# hassisPartSCH.net
KiCad netlist of a schematic drawn in Altium Designer
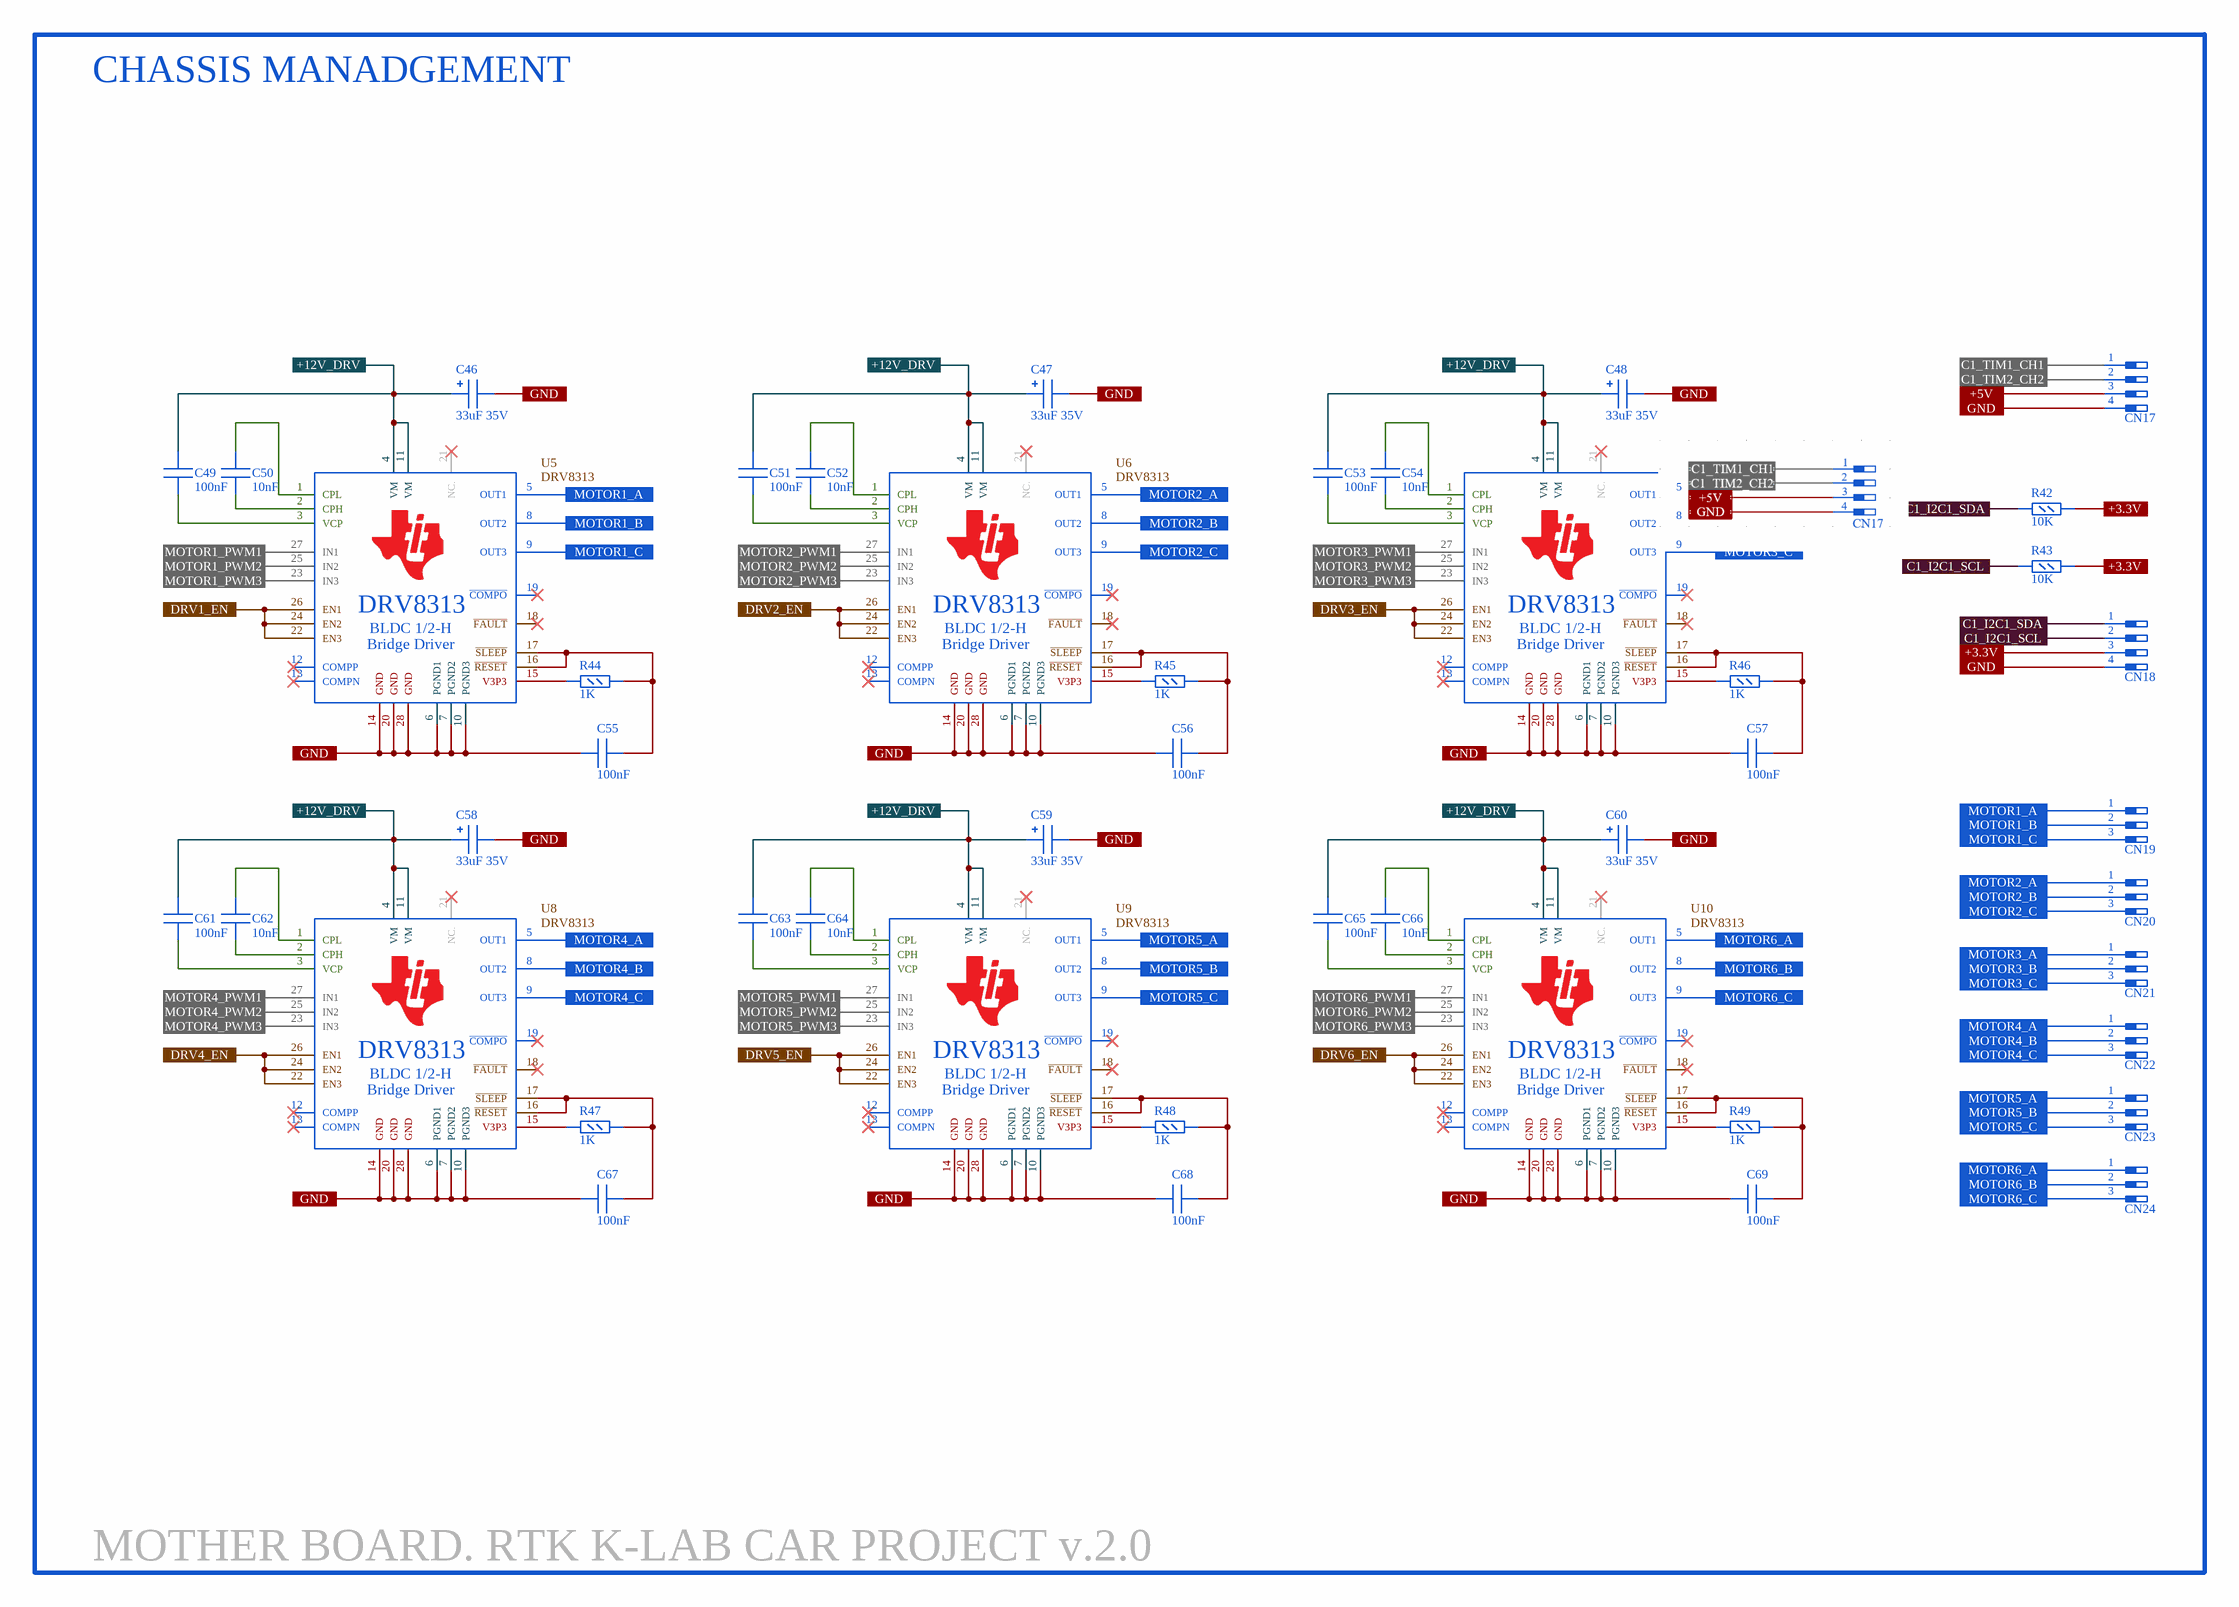
[diagram p0: СhassisPartSCH.SchDoc]

(export (version "E")
  (design (tool "Eeschema 10.0.6"))
  (components
    (comp (ref "C46")
      (value "33uF 35V")
      (footprint "CAP_TAN-B")
      (libsource (lib "CustomMillLib_Col") (part "Cap_Pol"))
    )
    (comp (ref "C47")
      (value "33uF 35V")
      (footprint "CAP_TAN-B")
      (libsource (lib "CustomMillLib_Col") (part "Cap_Pol"))
    )
    (comp (ref "C48")
      (value "33uF 35V")
      (footprint "CAP_TAN-B")
      (libsource (lib "CustomMillLib_Col") (part "Cap_Pol"))
    )
    (comp (ref "C49") (value "100nF") (footprint "C0603") (libsource (lib "CommonElements") (part "Cap")))
    (comp (ref "C50") (value "10nF") (footprint "C0603") (libsource (lib "CommonElements") (part "Cap")))
    (comp (ref "C51") (value "100nF") (footprint "C0603") (libsource (lib "CommonElements") (part "Cap")))
    (comp (ref "C52") (value "10nF") (footprint "C0603") (libsource (lib "CommonElements") (part "Cap")))
    (comp (ref "C53") (value "100nF") (footprint "C0603") (libsource (lib "CommonElements") (part "Cap")))
    (comp (ref "C54") (value "10nF") (footprint "C0603") (libsource (lib "CommonElements") (part "Cap")))
    (comp (ref "C55") (value "100nF") (footprint "C0603") (libsource (lib "CommonElements") (part "Cap")))
    (comp (ref "C56") (value "100nF") (footprint "C0603") (libsource (lib "CommonElements") (part "Cap")))
    (comp (ref "C57") (value "100nF") (footprint "C0603") (libsource (lib "CommonElements") (part "Cap")))
    (comp (ref "C58")
      (value "33uF 35V")
      (footprint "CAP_TAN-B")
      (libsource (lib "CustomMillLib_Col") (part "Cap_Pol"))
    )
    (comp (ref "C59")
      (value "33uF 35V")
      (footprint "CAP_TAN-B")
      (libsource (lib "CustomMillLib_Col") (part "Cap_Pol"))
    )
    (comp (ref "C60")
      (value "33uF 35V")
      (footprint "CAP_TAN-B")
      (libsource (lib "CustomMillLib_Col") (part "Cap_Pol"))
    )
    (comp (ref "C61") (value "100nF") (footprint "C0603") (libsource (lib "CommonElements") (part "Cap")))
    (comp (ref "C62") (value "10nF") (footprint "C0603") (libsource (lib "CommonElements") (part "Cap")))
    (comp (ref "C63") (value "100nF") (footprint "C0603") (libsource (lib "CommonElements") (part "Cap")))
    (comp (ref "C64") (value "10nF") (footprint "C0603") (libsource (lib "CommonElements") (part "Cap")))
    (comp (ref "C65") (value "100nF") (footprint "C0603") (libsource (lib "CommonElements") (part "Cap")))
    (comp (ref "C66") (value "10nF") (footprint "C0603") (libsource (lib "CommonElements") (part "Cap")))
    (comp (ref "C67") (value "100nF") (footprint "C0603") (libsource (lib "CommonElements") (part "Cap")))
    (comp (ref "C68") (value "100nF") (footprint "C0603") (libsource (lib "CommonElements") (part "Cap")))
    (comp (ref "C69") (value "100nF") (footprint "C0603") (libsource (lib "CommonElements") (part "Cap")))
    (comp (ref "CN17") (value "1x04") (footprint "4X1F") (libsource (lib "Connectors") (part "1x04")))
    (comp (ref "CN18") (value "1x04") (footprint "XH2.54-4PIN") (libsource (lib "Connectors") (part "1x04")))
    (comp (ref "CN19") (value "1x03") (footprint "H3-5.08") (libsource (lib "Connectors") (part "1x03")))
    (comp (ref "CN20") (value "1x03") (footprint "H3-5.08") (libsource (lib "Connectors") (part "1x03")))
    (comp (ref "CN21") (value "1x03") (footprint "H3-5.08") (libsource (lib "Connectors") (part "1x03")))
    (comp (ref "CN22") (value "1x03") (footprint "H3-5.08") (libsource (lib "Connectors") (part "1x03")))
    (comp (ref "CN23") (value "1x03") (footprint "H3-5.08") (libsource (lib "Connectors") (part "1x03")))
    (comp (ref "CN24") (value "1x03") (footprint "H3-5.08") (libsource (lib "Connectors") (part "1x03")))
    (comp (ref "R42") (value "10K") (footprint "R0603") (libsource (lib "CommonElements") (part "Res")))
    (comp (ref "R43") (value "10K") (footprint "R0603") (libsource (lib "CommonElements") (part "Res")))
    (comp (ref "R44") (value "1K") (footprint "R0603") (libsource (lib "CommonElements") (part "Res")))
    (comp (ref "R45") (value "1K") (footprint "R0603") (libsource (lib "CommonElements") (part "Res")))
    (comp (ref "R46") (value "1K") (footprint "R0603") (libsource (lib "CommonElements") (part "Res")))
    (comp (ref "R47") (value "1K") (footprint "R0603") (libsource (lib "CommonElements") (part "Res")))
    (comp (ref "R48") (value "1K") (footprint "R0603") (libsource (lib "CommonElements") (part "Res")))
    (comp (ref "R49") (value "1K") (footprint "R0603") (libsource (lib "CommonElements") (part "Res")))
    (comp (ref "U5")
      (value "DRV8313")
      (footprint "TSSOP28-TP")
      (libsource (lib "DigitalUnits") (part "DRV8313"))
    )
    (comp (ref "U6")
      (value "DRV8313")
      (footprint "TSSOP28-TP")
      (libsource (lib "DigitalUnits") (part "DRV8313"))
    )
    (comp (ref "U7")
      (value "DRV8313")
      (footprint "TSSOP28-TP")
      (libsource (lib "DigitalUnits") (part "DRV8313"))
    )
    (comp (ref "U8")
      (value "DRV8313")
      (footprint "TSSOP28-TP")
      (libsource (lib "DigitalUnits") (part "DRV8313"))
    )
    (comp (ref "U9")
      (value "DRV8313")
      (footprint "TSSOP28-TP")
      (libsource (lib "DigitalUnits") (part "DRV8313"))
    )
    (comp (ref "U10")
      (value "DRV8313")
      (footprint "TSSOP28-TP")
      (libsource (lib "DigitalUnits") (part "DRV8313"))
    )
  )
  (nets
    (net (code "1") (name "/+3.3V") (class "Default")
      (node (ref "CN18") (pin "3") (pintype "passive"))
      (node (ref "R42") (pin "2") (pinfunction "2_2") (pintype "passive"))
      (node (ref "R43") (pin "2") (pinfunction "2_2") (pintype "passive"))
    )
    (net (code "2") (name "/+5V") (class "Default") (node (ref "CN17") (pin "3") (pintype "passive")))
    (net (code "3") (name "/+12V_DRV") (class "Default")
      (node (ref "C46") (pin "1") (pinfunction "61_1") (pintype "passive"))
      (node (ref "C47") (pin "1") (pinfunction "61_1") (pintype "passive"))
      (node (ref "C48") (pin "1") (pinfunction "61_1") (pintype "passive"))
      (node (ref "C49") (pin "2") (pinfunction "62_2") (pintype "passive"))
      (node (ref "C51") (pin "2") (pinfunction "62_2") (pintype "passive"))
      (node (ref "C53") (pin "2") (pinfunction "62_2") (pintype "passive"))
      (node (ref "C58") (pin "1") (pinfunction "61_1") (pintype "passive"))
      (node (ref "C59") (pin "1") (pinfunction "61_1") (pintype "passive"))
      (node (ref "C60") (pin "1") (pinfunction "61_1") (pintype "passive"))
      (node (ref "C61") (pin "2") (pinfunction "62_2") (pintype "passive"))
      (node (ref "C63") (pin "2") (pinfunction "62_2") (pintype "passive"))
      (node (ref "C65") (pin "2") (pinfunction "62_2") (pintype "passive"))
      (node (ref "U10") (pin "11") (pinfunction "VM_11") (pintype "passive"))
      (node (ref "U10") (pin "4") (pinfunction "VM_4") (pintype "passive"))
      (node (ref "U5") (pin "11") (pinfunction "VM_11") (pintype "passive"))
      (node (ref "U5") (pin "4") (pinfunction "VM_4") (pintype "passive"))
      (node (ref "U6") (pin "11") (pinfunction "VM_11") (pintype "passive"))
      (node (ref "U6") (pin "4") (pinfunction "VM_4") (pintype "passive"))
      (node (ref "U7") (pin "11") (pinfunction "VM_11") (pintype "passive"))
      (node (ref "U7") (pin "4") (pinfunction "VM_4") (pintype "passive"))
      (node (ref "U8") (pin "11") (pinfunction "VM_11") (pintype "passive"))
      (node (ref "U8") (pin "4") (pinfunction "VM_4") (pintype "passive"))
      (node (ref "U9") (pin "11") (pinfunction "VM_11") (pintype "passive"))
      (node (ref "U9") (pin "4") (pinfunction "VM_4") (pintype "passive"))
    )
    (net (code "4") (name "/C1_I2C1_SCL") (class "Default")
      (node (ref "CN18") (pin "2") (pintype "passive"))
      (node (ref "R43") (pin "1") (pinfunction "2_1") (pintype "passive"))
    )
    (net (code "5") (name "/C1_I2C1_SDA") (class "Default")
      (node (ref "CN18") (pin "1") (pintype "passive"))
      (node (ref "R42") (pin "1") (pinfunction "2_1") (pintype "passive"))
    )
    (net (code "6") (name "/C1_TIM1_CH1") (class "Default") (node (ref "CN17") (pin "1") (pintype "passive")))
    (net (code "7") (name "/C1_TIM2_CH2") (class "Default") (node (ref "CN17") (pin "2") (pintype "passive")))
    (net (code "8") (name "/DRV1_EN") (class "Default")
      (node (ref "U5") (pin "22") (pinfunction "EN3_22") (pintype "passive"))
      (node (ref "U5") (pin "24") (pinfunction "EN2_24") (pintype "passive"))
      (node (ref "U5") (pin "26") (pinfunction "EN1_26") (pintype "passive"))
    )
    (net (code "9") (name "/DRV2_EN") (class "Default")
      (node (ref "U6") (pin "22") (pinfunction "EN3_22") (pintype "passive"))
      (node (ref "U6") (pin "24") (pinfunction "EN2_24") (pintype "passive"))
      (node (ref "U6") (pin "26") (pinfunction "EN1_26") (pintype "passive"))
    )
    (net (code "10") (name "/DRV3_EN") (class "Default")
      (node (ref "U7") (pin "22") (pinfunction "EN3_22") (pintype "passive"))
      (node (ref "U7") (pin "24") (pinfunction "EN2_24") (pintype "passive"))
      (node (ref "U7") (pin "26") (pinfunction "EN1_26") (pintype "passive"))
    )
    (net (code "11") (name "/DRV4_EN") (class "Default")
      (node (ref "U8") (pin "22") (pinfunction "EN3_22") (pintype "passive"))
      (node (ref "U8") (pin "24") (pinfunction "EN2_24") (pintype "passive"))
      (node (ref "U8") (pin "26") (pinfunction "EN1_26") (pintype "passive"))
    )
    (net (code "12") (name "/DRV5_EN") (class "Default")
      (node (ref "U9") (pin "22") (pinfunction "EN3_22") (pintype "passive"))
      (node (ref "U9") (pin "24") (pinfunction "EN2_24") (pintype "passive"))
      (node (ref "U9") (pin "26") (pinfunction "EN1_26") (pintype "passive"))
    )
    (net (code "13") (name "/DRV6_EN") (class "Default")
      (node (ref "U10") (pin "22") (pinfunction "EN3_22") (pintype "passive"))
      (node (ref "U10") (pin "24") (pinfunction "EN2_24") (pintype "passive"))
      (node (ref "U10") (pin "26") (pinfunction "EN1_26") (pintype "passive"))
    )
    (net (code "14") (name "/GND") (class "Default")
      (node (ref "C46") (pin "2") (pinfunction "62_2") (pintype "passive"))
      (node (ref "C47") (pin "2") (pinfunction "62_2") (pintype "passive"))
      (node (ref "C48") (pin "2") (pinfunction "62_2") (pintype "passive"))
      (node (ref "C55") (pin "1") (pinfunction "61_1") (pintype "passive"))
      (node (ref "C56") (pin "1") (pinfunction "61_1") (pintype "passive"))
      (node (ref "C57") (pin "1") (pinfunction "61_1") (pintype "passive"))
      (node (ref "C58") (pin "2") (pinfunction "62_2") (pintype "passive"))
      (node (ref "C59") (pin "2") (pinfunction "62_2") (pintype "passive"))
      (node (ref "C60") (pin "2") (pinfunction "62_2") (pintype "passive"))
      (node (ref "C67") (pin "1") (pinfunction "61_1") (pintype "passive"))
      (node (ref "C68") (pin "1") (pinfunction "61_1") (pintype "passive"))
      (node (ref "C69") (pin "1") (pinfunction "61_1") (pintype "passive"))
      (node (ref "CN17") (pin "4") (pintype "passive"))
      (node (ref "CN18") (pin "4") (pintype "passive"))
      (node (ref "U10") (pin "10") (pinfunction "PGND3_10") (pintype "passive"))
      (node (ref "U10") (pin "14") (pinfunction "GND_14") (pintype "passive"))
      (node (ref "U10") (pin "20") (pinfunction "GND_20") (pintype "passive"))
      (node (ref "U10") (pin "28") (pinfunction "GND_28") (pintype "passive"))
      (node (ref "U10") (pin "6") (pinfunction "PGND1_6") (pintype "passive"))
      (node (ref "U10") (pin "7") (pinfunction "PGND2_7") (pintype "passive"))
      (node (ref "U5") (pin "10") (pinfunction "PGND3_10") (pintype "passive"))
      (node (ref "U5") (pin "14") (pinfunction "GND_14") (pintype "passive"))
      (node (ref "U5") (pin "20") (pinfunction "GND_20") (pintype "passive"))
      (node (ref "U5") (pin "28") (pinfunction "GND_28") (pintype "passive"))
      (node (ref "U5") (pin "6") (pinfunction "PGND1_6") (pintype "passive"))
      (node (ref "U5") (pin "7") (pinfunction "PGND2_7") (pintype "passive"))
      (node (ref "U6") (pin "10") (pinfunction "PGND3_10") (pintype "passive"))
      (node (ref "U6") (pin "14") (pinfunction "GND_14") (pintype "passive"))
      (node (ref "U6") (pin "20") (pinfunction "GND_20") (pintype "passive"))
      (node (ref "U6") (pin "28") (pinfunction "GND_28") (pintype "passive"))
      (node (ref "U6") (pin "6") (pinfunction "PGND1_6") (pintype "passive"))
      (node (ref "U6") (pin "7") (pinfunction "PGND2_7") (pintype "passive"))
      (node (ref "U7") (pin "10") (pinfunction "PGND3_10") (pintype "passive"))
      (node (ref "U7") (pin "14") (pinfunction "GND_14") (pintype "passive"))
      (node (ref "U7") (pin "20") (pinfunction "GND_20") (pintype "passive"))
      (node (ref "U7") (pin "28") (pinfunction "GND_28") (pintype "passive"))
      (node (ref "U7") (pin "6") (pinfunction "PGND1_6") (pintype "passive"))
      (node (ref "U7") (pin "7") (pinfunction "PGND2_7") (pintype "passive"))
      (node (ref "U8") (pin "10") (pinfunction "PGND3_10") (pintype "passive"))
      (node (ref "U8") (pin "14") (pinfunction "GND_14") (pintype "passive"))
      (node (ref "U8") (pin "20") (pinfunction "GND_20") (pintype "passive"))
      (node (ref "U8") (pin "28") (pinfunction "GND_28") (pintype "passive"))
      (node (ref "U8") (pin "6") (pinfunction "PGND1_6") (pintype "passive"))
      (node (ref "U8") (pin "7") (pinfunction "PGND2_7") (pintype "passive"))
      (node (ref "U9") (pin "10") (pinfunction "PGND3_10") (pintype "passive"))
      (node (ref "U9") (pin "14") (pinfunction "GND_14") (pintype "passive"))
      (node (ref "U9") (pin "20") (pinfunction "GND_20") (pintype "passive"))
      (node (ref "U9") (pin "28") (pinfunction "GND_28") (pintype "passive"))
      (node (ref "U9") (pin "6") (pinfunction "PGND1_6") (pintype "passive"))
      (node (ref "U9") (pin "7") (pinfunction "PGND2_7") (pintype "passive"))
    )
    (net (code "15") (name "/MOTOR1_A") (class "Default")
      (node (ref "CN19") (pin "1") (pintype "passive"))
      (node (ref "U5") (pin "5") (pinfunction "OUT1_5") (pintype "passive"))
    )
    (net (code "16") (name "/MOTOR1_B") (class "Default")
      (node (ref "CN19") (pin "2") (pintype "passive"))
      (node (ref "U5") (pin "8") (pinfunction "OUT2_8") (pintype "passive"))
    )
    (net (code "17") (name "/MOTOR1_C") (class "Default")
      (node (ref "CN19") (pin "3") (pintype "passive"))
      (node (ref "U5") (pin "9") (pinfunction "OUT3_9") (pintype "passive"))
    )
    (net (code "18") (name "/MOTOR1_PWM1") (class "Default")
      (node (ref "U5") (pin "27") (pinfunction "IN1_27") (pintype "passive"))
    )
    (net (code "19") (name "/MOTOR1_PWM2") (class "Default")
      (node (ref "U5") (pin "25") (pinfunction "IN2_25") (pintype "passive"))
    )
    (net (code "20") (name "/MOTOR1_PWM3") (class "Default")
      (node (ref "U5") (pin "23") (pinfunction "IN3_23") (pintype "passive"))
    )
    (net (code "21") (name "/MOTOR2_A") (class "Default")
      (node (ref "CN20") (pin "1") (pintype "passive"))
      (node (ref "U6") (pin "5") (pinfunction "OUT1_5") (pintype "passive"))
    )
    (net (code "22") (name "/MOTOR2_B") (class "Default")
      (node (ref "CN20") (pin "2") (pintype "passive"))
      (node (ref "U6") (pin "8") (pinfunction "OUT2_8") (pintype "passive"))
    )
    (net (code "23") (name "/MOTOR2_C") (class "Default")
      (node (ref "CN20") (pin "3") (pintype "passive"))
      (node (ref "U6") (pin "9") (pinfunction "OUT3_9") (pintype "passive"))
    )
    (net (code "24") (name "/MOTOR2_PWM1") (class "Default")
      (node (ref "U6") (pin "27") (pinfunction "IN1_27") (pintype "passive"))
    )
    (net (code "25") (name "/MOTOR2_PWM2") (class "Default")
      (node (ref "U6") (pin "25") (pinfunction "IN2_25") (pintype "passive"))
    )
    (net (code "26") (name "/MOTOR2_PWM3") (class "Default")
      (node (ref "U6") (pin "23") (pinfunction "IN3_23") (pintype "passive"))
    )
    (net (code "27") (name "/MOTOR3_A") (class "Default")
      (node (ref "CN21") (pin "1") (pintype "passive"))
      (node (ref "U7") (pin "5") (pinfunction "OUT1_5") (pintype "passive"))
    )
    (net (code "28") (name "/MOTOR3_B") (class "Default")
      (node (ref "CN21") (pin "2") (pintype "passive"))
      (node (ref "U7") (pin "8") (pinfunction "OUT2_8") (pintype "passive"))
    )
    (net (code "29") (name "/MOTOR3_C") (class "Default")
      (node (ref "CN21") (pin "3") (pintype "passive"))
      (node (ref "U7") (pin "9") (pinfunction "OUT3_9") (pintype "passive"))
    )
    (net (code "30") (name "/MOTOR3_PWM1") (class "Default")
      (node (ref "U7") (pin "27") (pinfunction "IN1_27") (pintype "passive"))
    )
    (net (code "31") (name "/MOTOR3_PWM2") (class "Default")
      (node (ref "U7") (pin "25") (pinfunction "IN2_25") (pintype "passive"))
    )
    (net (code "32") (name "/MOTOR3_PWM3") (class "Default")
      (node (ref "U7") (pin "23") (pinfunction "IN3_23") (pintype "passive"))
    )
    (net (code "33") (name "/MOTOR4_A") (class "Default")
      (node (ref "CN22") (pin "1") (pintype "passive"))
      (node (ref "U8") (pin "5") (pinfunction "OUT1_5") (pintype "passive"))
    )
    (net (code "34") (name "/MOTOR4_B") (class "Default")
      (node (ref "CN22") (pin "2") (pintype "passive"))
      (node (ref "U8") (pin "8") (pinfunction "OUT2_8") (pintype "passive"))
    )
    (net (code "35") (name "/MOTOR4_C") (class "Default")
      (node (ref "CN22") (pin "3") (pintype "passive"))
      (node (ref "U8") (pin "9") (pinfunction "OUT3_9") (pintype "passive"))
    )
    (net (code "36") (name "/MOTOR4_PWM1") (class "Default")
      (node (ref "U8") (pin "27") (pinfunction "IN1_27") (pintype "passive"))
    )
    (net (code "37") (name "/MOTOR4_PWM2") (class "Default")
      (node (ref "U8") (pin "25") (pinfunction "IN2_25") (pintype "passive"))
    )
    (net (code "38") (name "/MOTOR4_PWM3") (class "Default")
      (node (ref "U8") (pin "23") (pinfunction "IN3_23") (pintype "passive"))
    )
    (net (code "39") (name "/MOTOR5_A") (class "Default")
      (node (ref "CN23") (pin "1") (pintype "passive"))
      (node (ref "U9") (pin "5") (pinfunction "OUT1_5") (pintype "passive"))
    )
    (net (code "40") (name "/MOTOR5_B") (class "Default")
      (node (ref "CN23") (pin "2") (pintype "passive"))
      (node (ref "U9") (pin "8") (pinfunction "OUT2_8") (pintype "passive"))
    )
    (net (code "41") (name "/MOTOR5_C") (class "Default")
      (node (ref "CN23") (pin "3") (pintype "passive"))
      (node (ref "U9") (pin "9") (pinfunction "OUT3_9") (pintype "passive"))
    )
    (net (code "42") (name "/MOTOR5_PWM1") (class "Default")
      (node (ref "U9") (pin "27") (pinfunction "IN1_27") (pintype "passive"))
    )
    (net (code "43") (name "/MOTOR5_PWM2") (class "Default")
      (node (ref "U9") (pin "25") (pinfunction "IN2_25") (pintype "passive"))
    )
    (net (code "44") (name "/MOTOR5_PWM3") (class "Default")
      (node (ref "U9") (pin "23") (pinfunction "IN3_23") (pintype "passive"))
    )
    (net (code "45") (name "/MOTOR6_A") (class "Default")
      (node (ref "CN24") (pin "1") (pintype "passive"))
      (node (ref "U10") (pin "5") (pinfunction "OUT1_5") (pintype "passive"))
    )
    (net (code "46") (name "/MOTOR6_B") (class "Default")
      (node (ref "CN24") (pin "2") (pintype "passive"))
      (node (ref "U10") (pin "8") (pinfunction "OUT2_8") (pintype "passive"))
    )
    (net (code "47") (name "/MOTOR6_C") (class "Default")
      (node (ref "CN24") (pin "3") (pintype "passive"))
      (node (ref "U10") (pin "9") (pinfunction "OUT3_9") (pintype "passive"))
    )
    (net (code "48") (name "/MOTOR6_PWM1") (class "Default")
      (node (ref "U10") (pin "27") (pinfunction "IN1_27") (pintype "passive"))
    )
    (net (code "49") (name "/MOTOR6_PWM2") (class "Default")
      (node (ref "U10") (pin "25") (pinfunction "IN2_25") (pintype "passive"))
    )
    (net (code "50") (name "/MOTOR6_PWM3") (class "Default")
      (node (ref "U10") (pin "23") (pinfunction "IN3_23") (pintype "passive"))
    )
    (net (code "51") (name "Net-(C49-61)") (class "Default")
      (node (ref "C49") (pin "1") (pinfunction "61_1") (pintype "passive"))
      (node (ref "U5") (pin "3") (pinfunction "VCP_3") (pintype "passive"))
    )
    (net (code "52") (name "Net-(C50-61)") (class "Default")
      (node (ref "C50") (pin "1") (pinfunction "61_1") (pintype "passive"))
      (node (ref "U5") (pin "2") (pinfunction "CPH_2") (pintype "passive"))
    )
    (net (code "53") (name "Net-(C50-62)") (class "Default")
      (node (ref "C50") (pin "2") (pinfunction "62_2") (pintype "passive"))
      (node (ref "U5") (pin "1") (pinfunction "CPL_1") (pintype "passive"))
    )
    (net (code "54") (name "Net-(C51-61)") (class "Default")
      (node (ref "C51") (pin "1") (pinfunction "61_1") (pintype "passive"))
      (node (ref "U6") (pin "3") (pinfunction "VCP_3") (pintype "passive"))
    )
    (net (code "55") (name "Net-(C52-61)") (class "Default")
      (node (ref "C52") (pin "1") (pinfunction "61_1") (pintype "passive"))
      (node (ref "U6") (pin "2") (pinfunction "CPH_2") (pintype "passive"))
    )
    (net (code "56") (name "Net-(C52-62)") (class "Default")
      (node (ref "C52") (pin "2") (pinfunction "62_2") (pintype "passive"))
      (node (ref "U6") (pin "1") (pinfunction "CPL_1") (pintype "passive"))
    )
    (net (code "57") (name "Net-(C53-61)") (class "Default")
      (node (ref "C53") (pin "1") (pinfunction "61_1") (pintype "passive"))
      (node (ref "U7") (pin "3") (pinfunction "VCP_3") (pintype "passive"))
    )
    (net (code "58") (name "Net-(C54-61)") (class "Default")
      (node (ref "C54") (pin "1") (pinfunction "61_1") (pintype "passive"))
      (node (ref "U7") (pin "2") (pinfunction "CPH_2") (pintype "passive"))
    )
    (net (code "59") (name "Net-(C54-62)") (class "Default")
      (node (ref "C54") (pin "2") (pinfunction "62_2") (pintype "passive"))
      (node (ref "U7") (pin "1") (pinfunction "CPL_1") (pintype "passive"))
    )
    (net (code "60") (name "Net-(C55-62)") (class "Default")
      (node (ref "C55") (pin "2") (pinfunction "62_2") (pintype "passive"))
      (node (ref "R44") (pin "2") (pinfunction "2_2") (pintype "passive"))
      (node (ref "U5") (pin "16") (pinfunction "RESET_16") (pintype "passive"))
      (node (ref "U5") (pin "17") (pinfunction "SLEEP_17") (pintype "passive"))
    )
    (net (code "61") (name "Net-(C56-62)") (class "Default")
      (node (ref "C56") (pin "2") (pinfunction "62_2") (pintype "passive"))
      (node (ref "R45") (pin "2") (pinfunction "2_2") (pintype "passive"))
      (node (ref "U6") (pin "16") (pinfunction "RESET_16") (pintype "passive"))
      (node (ref "U6") (pin "17") (pinfunction "SLEEP_17") (pintype "passive"))
    )
    (net (code "62") (name "Net-(C57-62)") (class "Default")
      (node (ref "C57") (pin "2") (pinfunction "62_2") (pintype "passive"))
      (node (ref "R46") (pin "2") (pinfunction "2_2") (pintype "passive"))
      (node (ref "U7") (pin "16") (pinfunction "RESET_16") (pintype "passive"))
      (node (ref "U7") (pin "17") (pinfunction "SLEEP_17") (pintype "passive"))
    )
    (net (code "63") (name "Net-(C61-61)") (class "Default")
      (node (ref "C61") (pin "1") (pinfunction "61_1") (pintype "passive"))
      (node (ref "U8") (pin "3") (pinfunction "VCP_3") (pintype "passive"))
    )
    (net (code "64") (name "Net-(C62-61)") (class "Default")
      (node (ref "C62") (pin "1") (pinfunction "61_1") (pintype "passive"))
      (node (ref "U8") (pin "2") (pinfunction "CPH_2") (pintype "passive"))
    )
    (net (code "65") (name "Net-(C62-62)") (class "Default")
      (node (ref "C62") (pin "2") (pinfunction "62_2") (pintype "passive"))
      (node (ref "U8") (pin "1") (pinfunction "CPL_1") (pintype "passive"))
    )
    (net (code "66") (name "Net-(C63-61)") (class "Default")
      (node (ref "C63") (pin "1") (pinfunction "61_1") (pintype "passive"))
      (node (ref "U9") (pin "3") (pinfunction "VCP_3") (pintype "passive"))
    )
    (net (code "67") (name "Net-(C64-61)") (class "Default")
      (node (ref "C64") (pin "1") (pinfunction "61_1") (pintype "passive"))
      (node (ref "U9") (pin "2") (pinfunction "CPH_2") (pintype "passive"))
    )
    (net (code "68") (name "Net-(C64-62)") (class "Default")
      (node (ref "C64") (pin "2") (pinfunction "62_2") (pintype "passive"))
      (node (ref "U9") (pin "1") (pinfunction "CPL_1") (pintype "passive"))
    )
    (net (code "69") (name "Net-(C65-61)") (class "Default")
      (node (ref "C65") (pin "1") (pinfunction "61_1") (pintype "passive"))
      (node (ref "U10") (pin "3") (pinfunction "VCP_3") (pintype "passive"))
    )
    (net (code "70") (name "Net-(C66-61)") (class "Default")
      (node (ref "C66") (pin "1") (pinfunction "61_1") (pintype "passive"))
      (node (ref "U10") (pin "2") (pinfunction "CPH_2") (pintype "passive"))
    )
    (net (code "71") (name "Net-(C66-62)") (class "Default")
      (node (ref "C66") (pin "2") (pinfunction "62_2") (pintype "passive"))
      (node (ref "U10") (pin "1") (pinfunction "CPL_1") (pintype "passive"))
    )
    (net (code "72") (name "Net-(C67-62)") (class "Default")
      (node (ref "C67") (pin "2") (pinfunction "62_2") (pintype "passive"))
      (node (ref "R47") (pin "2") (pinfunction "2_2") (pintype "passive"))
      (node (ref "U8") (pin "16") (pinfunction "RESET_16") (pintype "passive"))
      (node (ref "U8") (pin "17") (pinfunction "SLEEP_17") (pintype "passive"))
    )
    (net (code "73") (name "Net-(C68-62)") (class "Default")
      (node (ref "C68") (pin "2") (pinfunction "62_2") (pintype "passive"))
      (node (ref "R48") (pin "2") (pinfunction "2_2") (pintype "passive"))
      (node (ref "U9") (pin "16") (pinfunction "RESET_16") (pintype "passive"))
      (node (ref "U9") (pin "17") (pinfunction "SLEEP_17") (pintype "passive"))
    )
    (net (code "74") (name "Net-(C69-62)") (class "Default")
      (node (ref "C69") (pin "2") (pinfunction "62_2") (pintype "passive"))
      (node (ref "R49") (pin "2") (pinfunction "2_2") (pintype "passive"))
      (node (ref "U10") (pin "16") (pinfunction "RESET_16") (pintype "passive"))
      (node (ref "U10") (pin "17") (pinfunction "SLEEP_17") (pintype "passive"))
    )
    (net (code "75") (name "Net-(U5-V3P3)") (class "Default")
      (node (ref "R44") (pin "1") (pinfunction "2_1") (pintype "passive"))
      (node (ref "U5") (pin "15") (pinfunction "V3P3_15") (pintype "passive"))
    )
    (net (code "76") (name "Net-(U6-V3P3)") (class "Default")
      (node (ref "R45") (pin "1") (pinfunction "2_1") (pintype "passive"))
      (node (ref "U6") (pin "15") (pinfunction "V3P3_15") (pintype "passive"))
    )
    (net (code "77") (name "Net-(U7-V3P3)") (class "Default")
      (node (ref "R46") (pin "1") (pinfunction "2_1") (pintype "passive"))
      (node (ref "U7") (pin "15") (pinfunction "V3P3_15") (pintype "passive"))
    )
    (net (code "78") (name "Net-(U8-V3P3)") (class "Default")
      (node (ref "R47") (pin "1") (pinfunction "2_1") (pintype "passive"))
      (node (ref "U8") (pin "15") (pinfunction "V3P3_15") (pintype "passive"))
    )
    (net (code "79") (name "Net-(U9-V3P3)") (class "Default")
      (node (ref "R48") (pin "1") (pinfunction "2_1") (pintype "passive"))
      (node (ref "U9") (pin "15") (pinfunction "V3P3_15") (pintype "passive"))
    )
    (net (code "80") (name "Net-(U10-V3P3)") (class "Default")
      (node (ref "R49") (pin "1") (pinfunction "2_1") (pintype "passive"))
      (node (ref "U10") (pin "15") (pinfunction "V3P3_15") (pintype "passive"))
    )
    (net (code "81") (name "unconnected-(U5-COMPN-Pad13)") (class "Default")
      (node (ref "U5") (pin "13") (pinfunction "COMPN_13") (pintype "passive+no_connect"))
    )
    (net (code "82") (name "unconnected-(U5-COMPO-Pad19)") (class "Default")
      (node (ref "U5") (pin "19") (pinfunction "COMPO_19") (pintype "passive+no_connect"))
    )
    (net (code "83") (name "unconnected-(U5-COMPP-Pad12)") (class "Default")
      (node (ref "U5") (pin "12") (pinfunction "COMPP_12") (pintype "passive+no_connect"))
    )
    (net (code "84") (name "unconnected-(U5-FAULT-Pad18)") (class "Default")
      (node (ref "U5") (pin "18") (pinfunction "FAULT_18") (pintype "passive+no_connect"))
    )
    (net (code "85") (name "unconnected-(U5-NC.-Pad21)") (class "Default")
      (node (ref "U5") (pin "21") (pinfunction "NC._21") (pintype "passive+no_connect"))
    )
    (net (code "86") (name "unconnected-(U6-COMPN-Pad13)") (class "Default")
      (node (ref "U6") (pin "13") (pinfunction "COMPN_13") (pintype "passive+no_connect"))
    )
    (net (code "87") (name "unconnected-(U6-COMPO-Pad19)") (class "Default")
      (node (ref "U6") (pin "19") (pinfunction "COMPO_19") (pintype "passive+no_connect"))
    )
    (net (code "88") (name "unconnected-(U6-COMPP-Pad12)") (class "Default")
      (node (ref "U6") (pin "12") (pinfunction "COMPP_12") (pintype "passive+no_connect"))
    )
    (net (code "89") (name "unconnected-(U6-FAULT-Pad18)") (class "Default")
      (node (ref "U6") (pin "18") (pinfunction "FAULT_18") (pintype "passive+no_connect"))
    )
    (net (code "90") (name "unconnected-(U6-NC.-Pad21)") (class "Default")
      (node (ref "U6") (pin "21") (pinfunction "NC._21") (pintype "passive+no_connect"))
    )
    (net (code "91") (name "unconnected-(U7-COMPN-Pad13)") (class "Default")
      (node (ref "U7") (pin "13") (pinfunction "COMPN_13") (pintype "passive+no_connect"))
    )
    (net (code "92") (name "unconnected-(U7-COMPO-Pad19)") (class "Default")
      (node (ref "U7") (pin "19") (pinfunction "COMPO_19") (pintype "passive+no_connect"))
    )
    (net (code "93") (name "unconnected-(U7-COMPP-Pad12)") (class "Default")
      (node (ref "U7") (pin "12") (pinfunction "COMPP_12") (pintype "passive+no_connect"))
    )
    (net (code "94") (name "unconnected-(U7-FAULT-Pad18)") (class "Default")
      (node (ref "U7") (pin "18") (pinfunction "FAULT_18") (pintype "passive+no_connect"))
    )
    (net (code "95") (name "unconnected-(U7-NC.-Pad21)") (class "Default")
      (node (ref "U7") (pin "21") (pinfunction "NC._21") (pintype "passive+no_connect"))
    )
    (net (code "96") (name "unconnected-(U8-COMPN-Pad13)") (class "Default")
      (node (ref "U8") (pin "13") (pinfunction "COMPN_13") (pintype "passive+no_connect"))
    )
    (net (code "97") (name "unconnected-(U8-COMPO-Pad19)") (class "Default")
      (node (ref "U8") (pin "19") (pinfunction "COMPO_19") (pintype "passive+no_connect"))
    )
    (net (code "98") (name "unconnected-(U8-COMPP-Pad12)") (class "Default")
      (node (ref "U8") (pin "12") (pinfunction "COMPP_12") (pintype "passive+no_connect"))
    )
    (net (code "99") (name "unconnected-(U8-FAULT-Pad18)") (class "Default")
      (node (ref "U8") (pin "18") (pinfunction "FAULT_18") (pintype "passive+no_connect"))
    )
    (net (code "100") (name "unconnected-(U8-NC.-Pad21)") (class "Default")
      (node (ref "U8") (pin "21") (pinfunction "NC._21") (pintype "passive+no_connect"))
    )
    (net (code "101") (name "unconnected-(U9-COMPN-Pad13)") (class "Default")
      (node (ref "U9") (pin "13") (pinfunction "COMPN_13") (pintype "passive+no_connect"))
    )
    (net (code "102") (name "unconnected-(U9-COMPO-Pad19)") (class "Default")
      (node (ref "U9") (pin "19") (pinfunction "COMPO_19") (pintype "passive+no_connect"))
    )
    (net (code "103") (name "unconnected-(U9-COMPP-Pad12)") (class "Default")
      (node (ref "U9") (pin "12") (pinfunction "COMPP_12") (pintype "passive+no_connect"))
    )
    (net (code "104") (name "unconnected-(U9-FAULT-Pad18)") (class "Default")
      (node (ref "U9") (pin "18") (pinfunction "FAULT_18") (pintype "passive+no_connect"))
    )
    (net (code "105") (name "unconnected-(U9-NC.-Pad21)") (class "Default")
      (node (ref "U9") (pin "21") (pinfunction "NC._21") (pintype "passive+no_connect"))
    )
    (net (code "106") (name "unconnected-(U10-COMPN-Pad13)") (class "Default")
      (node (ref "U10") (pin "13") (pinfunction "COMPN_13") (pintype "passive+no_connect"))
    )
    (net (code "107") (name "unconnected-(U10-COMPO-Pad19)") (class "Default")
      (node (ref "U10") (pin "19") (pinfunction "COMPO_19") (pintype "passive+no_connect"))
    )
    (net (code "108") (name "unconnected-(U10-COMPP-Pad12)") (class "Default")
      (node (ref "U10") (pin "12") (pinfunction "COMPP_12") (pintype "passive+no_connect"))
    )
    (net (code "109") (name "unconnected-(U10-FAULT-Pad18)") (class "Default")
      (node (ref "U10") (pin "18") (pinfunction "FAULT_18") (pintype "passive+no_connect"))
    )
    (net (code "110") (name "unconnected-(U10-NC.-Pad21)") (class "Default")
      (node (ref "U10") (pin "21") (pinfunction "NC._21") (pintype "passive+no_connect"))
    )
  )
)
